# tricorder-front-sensors-mk-1_0.net
KiCad netlist of a schematic drawn in EAGLE
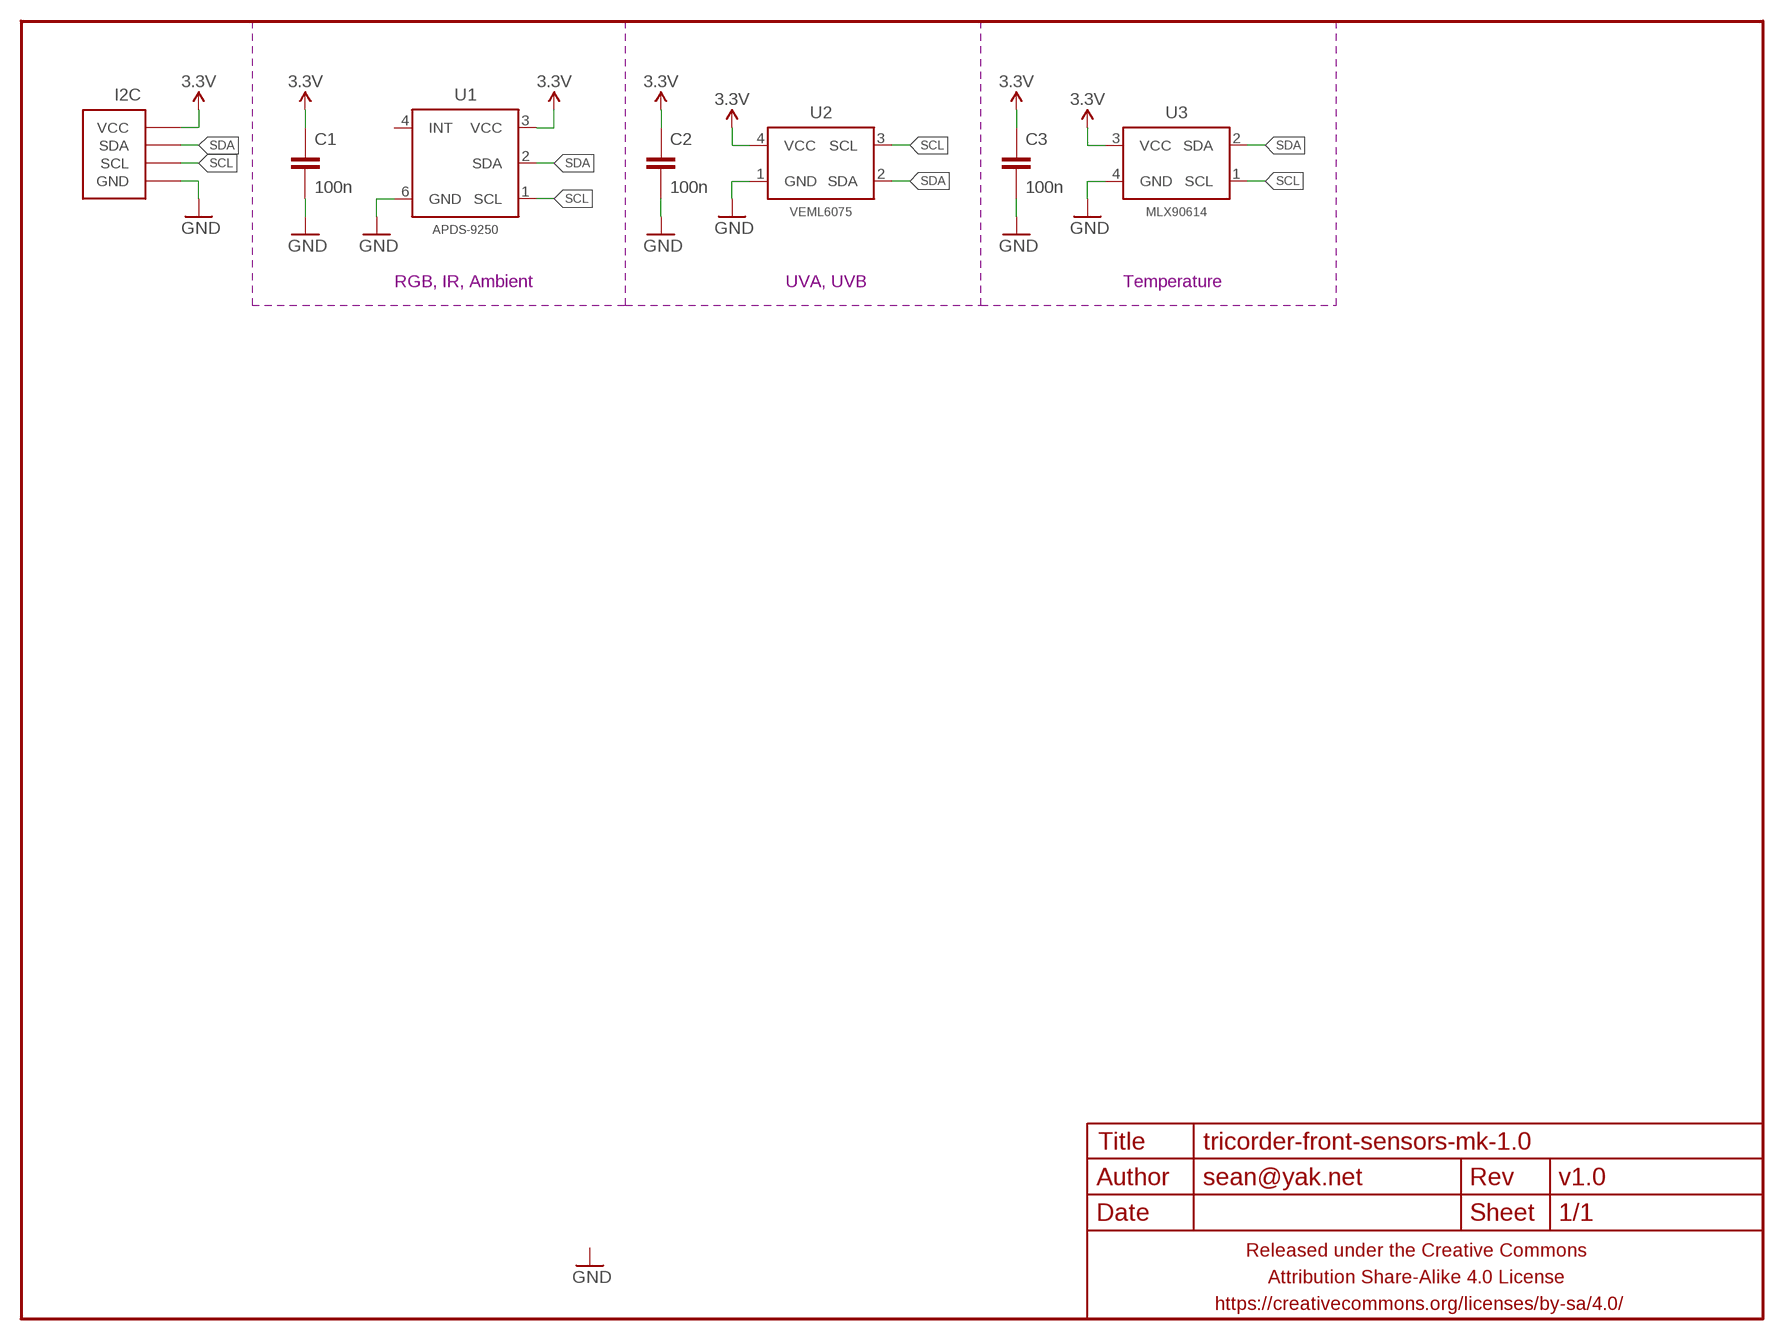
[diagram p0: schematic, sheet 1]

(export (version "E")
  (design (tool "Eeschema 10.0.6"))
  (components
    (comp (ref "C1")
      (value "100n")
      (footprint "eagle-import:C0603")
      (libsource (lib "eagle-import") (part "CAPACITOR-CERAMICC0603"))
    )
    (comp (ref "C2")
      (value "100n")
      (footprint "eagle-import:C0603")
      (libsource (lib "eagle-import") (part "CAPACITOR-CERAMICC0603"))
    )
    (comp (ref "C3")
      (value "100n")
      (footprint "eagle-import:C0603")
      (libsource (lib "eagle-import") (part "CAPACITOR-CERAMICC0603"))
    )
    (comp (ref "FRAME1")
      (value "FRAME-LETTERNO_PACKAGE")
      (footprint "eagle-import:DUMMY")
      (fields (field (name "DESIGNER") "sean@yak.net") (field (name "VERSION") "v1.0"))
      (libsource (lib "eagle-import") (part "FRAME-LETTERNO_PACKAGE"))
    )
    (comp (ref "I2C")
      (value "M04-I2CJST-4-PH-VERT-CENTERED-I2C")
      (footprint "eagle-import:JST-4-PH-VERT-PTH-CENTERED-I2C")
      (libsource (lib "eagle-import") (part "M04-I2CJST-4-PH-VERT-CENTERED-I2C"))
    )
    (comp (ref "U1")
      (value "APDS-9250")
      (footprint "eagle-import:APDS-9250")
      (libsource (lib "eagle-import") (part "APDS-9250"))
    )
    (comp (ref "U2")
      (value "VEML6075")
      (footprint "eagle-import:OPLGA4")
      (libsource (lib "eagle-import") (part "VEML6075"))
    )
    (comp (ref "U3")
      (value "MLX90614")
      (footprint "eagle-import:TO-39-4")
      (libsource (lib "eagle-import") (part "MLX90614"))
    )
  )
  (nets
    (net (code "1") (name "3.3V") (class "Default")
      (node (ref "C1") (pin "1") (pinfunction "1_1") (pintype "passive"))
      (node (ref "C2") (pin "1") (pinfunction "1_1") (pintype "passive"))
      (node (ref "C3") (pin "1") (pinfunction "1_1") (pintype "passive"))
      (node (ref "I2C") (pin "2") (pinfunction "VCC_2") (pintype "bidirectional"))
      (node (ref "U1") (pin "3") (pinfunction "VCC_3") (pintype "bidirectional"))
      (node (ref "U2") (pin "4") (pinfunction "VCC_4") (pintype "bidirectional"))
      (node (ref "U3") (pin "3") (pinfunction "VCC_3") (pintype "bidirectional"))
    )
    (net (code "2") (name "GND") (class "Default")
      (node (ref "C1") (pin "2") (pinfunction "2_2") (pintype "passive"))
      (node (ref "C2") (pin "2") (pinfunction "2_2") (pintype "passive"))
      (node (ref "C3") (pin "2") (pinfunction "2_2") (pintype "passive"))
      (node (ref "I2C") (pin "1") (pinfunction "GND_1") (pintype "bidirectional"))
      (node (ref "U1") (pin "6") (pinfunction "GND_6") (pintype "bidirectional"))
      (node (ref "U2") (pin "1") (pinfunction "GND_1") (pintype "bidirectional"))
      (node (ref "U3") (pin "4") (pinfunction "GND_4") (pintype "bidirectional"))
    )
    (net (code "3") (name "SCL") (class "Default")
      (node (ref "I2C") (pin "4") (pinfunction "SCL_4") (pintype "bidirectional"))
      (node (ref "U1") (pin "1") (pinfunction "SCL_1") (pintype "bidirectional"))
      (node (ref "U2") (pin "3") (pinfunction "SCL_3") (pintype "bidirectional"))
      (node (ref "U3") (pin "1") (pinfunction "SCL_1") (pintype "bidirectional"))
    )
    (net (code "4") (name "SDA") (class "Default")
      (node (ref "I2C") (pin "3") (pinfunction "SDA_3") (pintype "bidirectional"))
      (node (ref "U1") (pin "2") (pinfunction "SDA_2") (pintype "bidirectional"))
      (node (ref "U2") (pin "2") (pinfunction "SDA_2") (pintype "bidirectional"))
      (node (ref "U3") (pin "2") (pinfunction "SDA_2") (pintype "bidirectional"))
    )
    (net (code "5") (name "unconnected-(U1-INT-Pad4)") (class "Default")
      (node (ref "U1") (pin "4") (pinfunction "INT_4") (pintype "bidirectional"))
    )
  )
)
